# MSP430_Programmer_QFP16.net
KiCad netlist of a schematic drawn in EAGLE
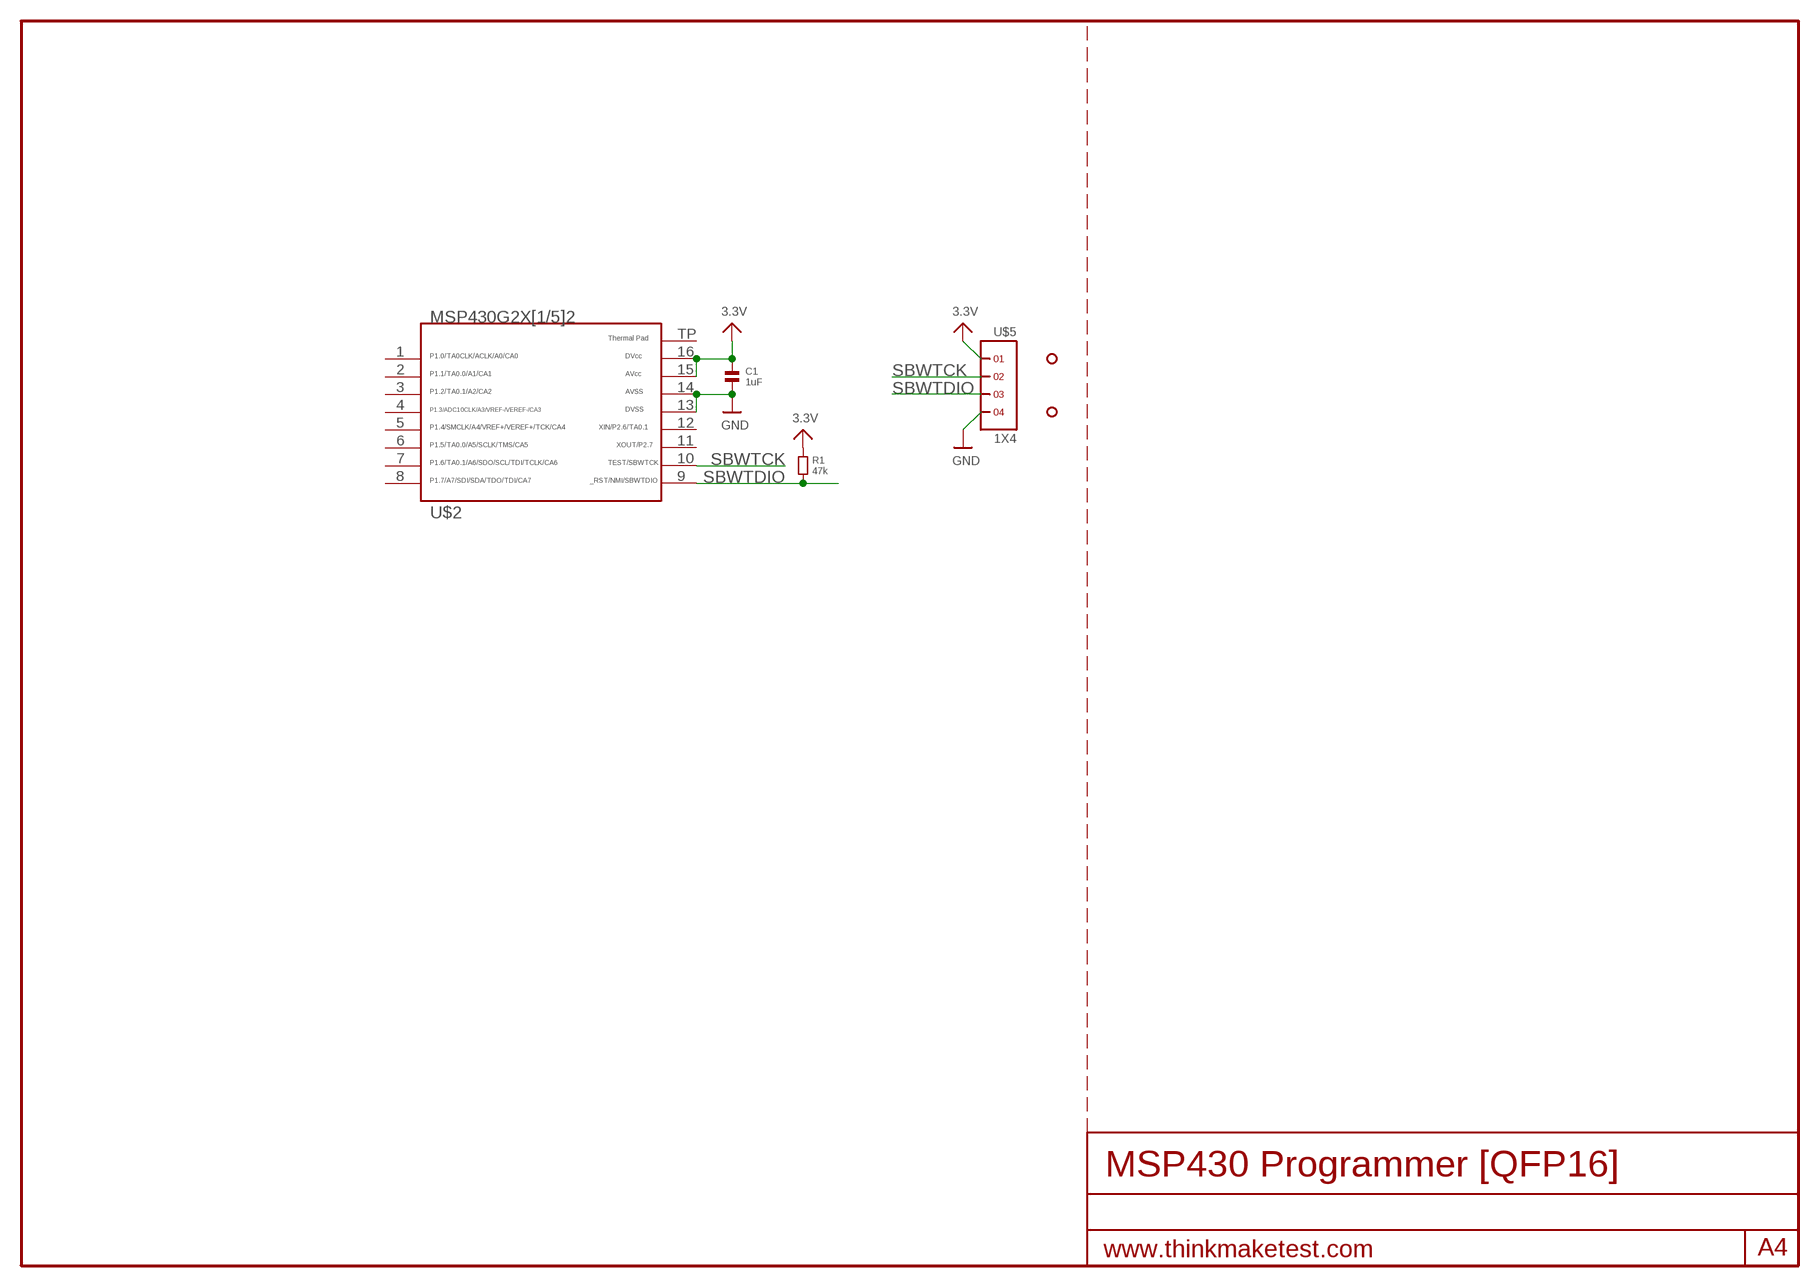
[diagram p0: schematic, sheet 1]

(export (version "E")
  (design (tool "Eeschema 10.0.6"))
  (components
    (comp (ref "C1")
      (value "1uF")
      (footprint "eagle-import:0805")
      (libsource (lib "eagle-import") (part "CAPACITOR.0805"))
    )
    (comp (ref "R1")
      (value "47k")
      (footprint "eagle-import:0805")
      (libsource (lib "eagle-import") (part "RESISTOR.0805"))
    )
    (comp (ref "U$2")
      (value "G2X[1/5]2---RSA16")
      (footprint "eagle-import:RSA16")
      (libsource (lib "eagle-import") (part "G2X[1/5]2---RSA16"))
    )
    (comp (ref "U$5")
      (value "1X4")
      (footprint "eagle-import:1X4")
      (libsource (lib "eagle-import") (part "1X4"))
    )
    (comp (ref "U$7")
      (value "HOLE.2MM")
      (footprint "eagle-import:2MM")
      (libsource (lib "eagle-import") (part "HOLE.2MM"))
    )
    (comp (ref "U$8")
      (value "HOLE.2MM")
      (footprint "eagle-import:2MM")
      (libsource (lib "eagle-import") (part "HOLE.2MM"))
    )
  )
  (nets
    (net (code "1") (name "/SBWTCK") (class "Default")
      (node (ref "U$2") (pin "10") (pinfunction "10_10") (pintype "bidirectional"))
      (node (ref "U$5") (pin "2") (pinfunction "2_2") (pintype "bidirectional"))
    )
    (net (code "2") (name "/SBWTDIO") (class "Default")
      (node (ref "R1") (pin "2") (pinfunction "2_2") (pintype "bidirectional"))
      (node (ref "U$2") (pin "9") (pinfunction "9_9") (pintype "bidirectional"))
      (node (ref "U$5") (pin "3") (pinfunction "3_3") (pintype "bidirectional"))
    )
    (net (code "3") (name "3.3V") (class "Default")
      (node (ref "C1") (pin "1") (pinfunction "1_1") (pintype "bidirectional"))
      (node (ref "R1") (pin "1") (pinfunction "1_1") (pintype "bidirectional"))
      (node (ref "U$2") (pin "15") (pinfunction "15_15") (pintype "bidirectional"))
      (node (ref "U$2") (pin "16") (pinfunction "16_16") (pintype "bidirectional"))
      (node (ref "U$5") (pin "1") (pinfunction "1_1") (pintype "bidirectional"))
    )
    (net (code "4") (name "GND") (class "Default")
      (node (ref "C1") (pin "2") (pinfunction "2_2") (pintype "bidirectional"))
      (node (ref "U$2") (pin "13") (pinfunction "13_13") (pintype "bidirectional"))
      (node (ref "U$2") (pin "14") (pinfunction "14_14") (pintype "bidirectional"))
      (node (ref "U$5") (pin "4") (pinfunction "4_4") (pintype "bidirectional"))
    )
    (net (code "5") (name "unconnected-(U$2-Pad1)") (class "Default")
      (node (ref "U$2") (pin "1") (pinfunction "1_1") (pintype "bidirectional"))
    )
    (net (code "6") (name "unconnected-(U$2-Pad2)") (class "Default")
      (node (ref "U$2") (pin "2") (pinfunction "2_2") (pintype "bidirectional"))
    )
    (net (code "7") (name "unconnected-(U$2-Pad3)") (class "Default")
      (node (ref "U$2") (pin "3") (pinfunction "3_3") (pintype "bidirectional"))
    )
    (net (code "8") (name "unconnected-(U$2-Pad4)") (class "Default")
      (node (ref "U$2") (pin "4") (pinfunction "4_4") (pintype "bidirectional"))
    )
    (net (code "9") (name "unconnected-(U$2-Pad5)") (class "Default")
      (node (ref "U$2") (pin "5") (pinfunction "5_5") (pintype "bidirectional"))
    )
    (net (code "10") (name "unconnected-(U$2-Pad6)") (class "Default")
      (node (ref "U$2") (pin "6") (pinfunction "6_6") (pintype "bidirectional"))
    )
    (net (code "11") (name "unconnected-(U$2-Pad7)") (class "Default")
      (node (ref "U$2") (pin "7") (pinfunction "7_7") (pintype "bidirectional"))
    )
    (net (code "12") (name "unconnected-(U$2-Pad8)") (class "Default")
      (node (ref "U$2") (pin "8") (pinfunction "8_8") (pintype "bidirectional"))
    )
    (net (code "13") (name "unconnected-(U$2-Pad11)") (class "Default")
      (node (ref "U$2") (pin "11") (pinfunction "11_11") (pintype "bidirectional"))
    )
    (net (code "14") (name "unconnected-(U$2-Pad12)") (class "Default")
      (node (ref "U$2") (pin "12") (pinfunction "12_12") (pintype "bidirectional"))
    )
    (net (code "15") (name "unconnected-(U$2-PadTP)") (class "Default")
      (node (ref "U$2") (pin "TP") (pinfunction "TP_TP") (pintype "bidirectional"))
    )
  )
)
